# IAMP.net
KiCad netlist of a schematic drawn in Altium Designer
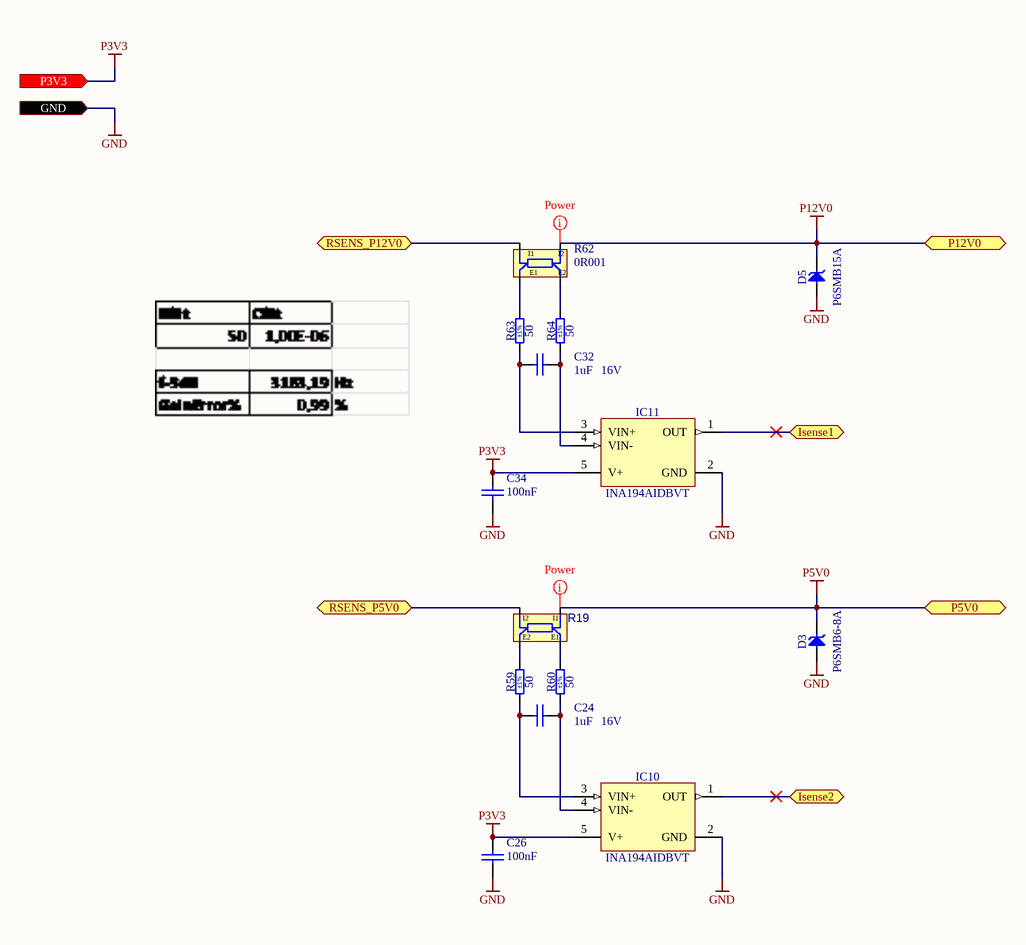
[diagram p0: IAMP.SchDoc]

(export (version "E")
  (design (tool "Eeschema 10.0.6"))
  (components
    (comp (ref "C24")
      (value "1uF")
      (footprint "CAPC1608X87N")
      (description "Non-polarised capacitor")
      (fields
        (field (name "PART NUMBER") "CC0603_1UF_16V_10%_X7R")
        (field (name "VOLTAGE") "16V")
        (field (name "TOLERANCE") "±10%")
        (field (name "AUTHOR") "CERN DEM JLC")
      )
      (libsource (lib "Capacitors") (part "Capacitor - non polarized"))
    )
    (comp (ref "C26")
      (value "100nF")
      (footprint "CAPC1608X87N")
      (description "Non-polarised capacitor")
      (fields
        (field (name "PART NUMBER") "CC0603_100NF_50V_10%_X5R")
        (field (name "VOLTAGE") "50V")
        (field (name "AUTHOR") "CERN DEM MR")
      )
      (libsource (lib "Capacitors") (part "Capacitor - non polarized"))
    )
    (comp (ref "C32")
      (value "1uF")
      (footprint "CAPC1608X87N")
      (description "Non-polarised capacitor")
      (fields
        (field (name "PART NUMBER") "CC0603_1UF_16V_10%_X7R")
        (field (name "VOLTAGE") "16V")
        (field (name "TOLERANCE") "±10%")
        (field (name "AUTHOR") "CERN DEM JLC")
      )
      (libsource (lib "Capacitors") (part "Capacitor - non polarized"))
    )
    (comp (ref "C34")
      (value "100nF")
      (footprint "CAPC1608X87N")
      (description "Non-polarised capacitor")
      (fields
        (field (name "PART NUMBER") "CC0603_100NF_50V_10%_X5R")
        (field (name "VOLTAGE") "50V")
        (field (name "AUTHOR") "CERN DEM MR")
      )
      (libsource (lib "Capacitors") (part "Capacitor - non polarized"))
    )
    (comp (ref "D3")
      (value "P6SMB6-8A")
      (footprint "DIOM5436X261N")
      (description "10.5V Clamp 58.1A Ipp Tvs Diode Surface Mount SMB")
      (fields (field (name "VOLTAGE") "15V") (field (name "POWER") "600W") (field (name "AUTHOR") "LPA"))
      (libsource (lib "DIOT_PSU") (part "P6SMB6-8A"))
    )
    (comp (ref "D5")
      (value "P6SMB15A")
      (footprint "DIOM5436X261N")
      (description "Transient Voltage Suppressor Diode (Uni-Directional)")
      (fields
        (field (name "VOLTAGE") "15V")
        (field (name "POWER") "600W")
        (field (name "AUTHOR") "CERN DEM JLC")
      )
      (libsource (lib "ICs And Semiconductors") (part "Diode TVS Uni-Directional"))
    )
    (comp (ref "IC10")
      (value "INA194AIDBVT")
      (footprint "SOT95P280X145-5N")
      (description "Current Shunt Monitor -16V to +80V Common-Mode Range")
      (fields
        (field (name "MANUFACTURER") "TEXAS INSTRUMENTS")
        (field (name "MANUFACTURER PART NUMBER") "INA194AIDBV")
        (field (name "AUTHOR") "CERN DEM JLC")
      )
      (libsource (lib "ICs And Semiconductors") (part "INA194"))
    )
    (comp (ref "IC11")
      (value "INA194AIDBVT")
      (footprint "SOT95P280X145-5N")
      (description "Current Shunt Monitor -16V to +80V Common-Mode Range")
      (fields
        (field (name "MANUFACTURER") "TEXAS INSTRUMENTS")
        (field (name "MANUFACTURER PART NUMBER") "INA194AIDBV")
        (field (name "AUTHOR") "CERN DEM JLC")
      )
      (libsource (lib "ICs And Semiconductors") (part "INA194"))
    )
    (comp (ref "R19")
      (value "FC4TR100DER")
      (footprint "FC4TR100DER")
      (description "Fixed Resistor, Metal Foil, 0.5W, 0.1ohm, 0.5% +/-Tol, 50ppm/Cel, Surface Mount, 1206")
      (libsource (lib "TechnoSystem Workspace") (part "FC4TR100DER"))
    )
    (comp (ref "R59")
      (value "50")
      (footprint "RESC1608X55N")
      (description "Resistor - 1%")
      (fields
        (field (name "TOLERANCE") "±1%")
        (field (name "PART NUMBER") "R0603_50R_1%_0.1W_100PPM")
        (field (name "POWER") "0.1W")
        (field (name "AUTHOR") "CERN DEM MR")
      )
      (libsource (lib "Resistors") (part "Resistor - 1%"))
    )
    (comp (ref "R60")
      (value "50")
      (footprint "RESC1608X55N")
      (description "Resistor - 1%")
      (fields
        (field (name "TOLERANCE") "±1%")
        (field (name "PART NUMBER") "R0603_50R_1%_0.1W_100PPM")
        (field (name "POWER") "0.1W")
        (field (name "AUTHOR") "CERN DEM MR")
      )
      (libsource (lib "Resistors") (part "Resistor - 1%"))
    )
    (comp (ref "R62")
      (value "0R001")
      (footprint "RES_VISHAY_WSL3637_0R001-0R0019")
      (description "Power and Current Sensing Resistor")
      (fields
        (field (name "PART NUMBER") "R3637_0R001_1%_3W_50PPM_VISHAY_WSL3637")
        (field (name "POWER") "3W")
        (field (name "AUTHOR") "CERN DEM MR")
      )
      (libsource (lib "Resistors") (part "Current Sense Resistor"))
    )
    (comp (ref "R63")
      (value "50")
      (footprint "RESC1608X55N")
      (description "Resistor - 1%")
      (fields
        (field (name "TOLERANCE") "±1%")
        (field (name "PART NUMBER") "R0603_50R_1%_0.1W_100PPM")
        (field (name "POWER") "0.1W")
        (field (name "AUTHOR") "CERN DEM MR")
      )
      (libsource (lib "Resistors") (part "Resistor - 1%"))
    )
    (comp (ref "R64")
      (value "50")
      (footprint "RESC1608X55N")
      (description "Resistor - 1%")
      (fields
        (field (name "TOLERANCE") "±1%")
        (field (name "PART NUMBER") "R0603_50R_1%_0.1W_100PPM")
        (field (name "POWER") "0.1W")
        (field (name "AUTHOR") "CERN DEM MR")
      )
      (libsource (lib "Resistors") (part "Resistor - 1%"))
    )
  )
  (nets
    (net (code "1") (name "/Isense1") (class "Default")
      (node (ref "IC11") (pin "1") (pinfunction "OUT_1") (pintype "output"))
    )
    (net (code "2") (name "/Isense2") (class "Default")
      (node (ref "IC10") (pin "1") (pinfunction "OUT_1") (pintype "output"))
    )
    (net (code "3") (name "/RSENS_P5V0") (class "Default")
      (node (ref "R19") (pin "I2") (pinfunction "I2_I2") (pintype "passive"))
    )
    (net (code "4") (name "/RSENS_P12V0") (class "Default")
      (node (ref "R62") (pin "I1") (pinfunction "I1_I1") (pintype "passive"))
    )
    (net (code "5") (name "GND") (class "Default")
      (node (ref "C26") (pin "2") (pinfunction "2_2") (pintype "passive"))
      (node (ref "C34") (pin "2") (pinfunction "2_2") (pintype "passive"))
      (node (ref "D3") (pin "2") (pinfunction "A_2") (pintype "passive"))
      (node (ref "D5") (pin "2") (pinfunction "A_2") (pintype "passive"))
      (node (ref "IC10") (pin "2") (pinfunction "GND_2") (pintype "power_in"))
      (node (ref "IC11") (pin "2") (pinfunction "GND_2") (pintype "power_in"))
    )
    (net (code "6") (name "Net-(IC10-VIN+)") (class "Default")
      (node (ref "C24") (pin "1") (pinfunction "1_1") (pintype "passive"))
      (node (ref "IC10") (pin "3") (pinfunction "VIN+_3") (pintype "input"))
      (node (ref "R59") (pin "1") (pinfunction "1_1") (pintype "passive"))
    )
    (net (code "7") (name "Net-(IC10-VIN-)") (class "Default")
      (node (ref "C24") (pin "2") (pinfunction "2_2") (pintype "passive"))
      (node (ref "IC10") (pin "4") (pinfunction "VIN-_4") (pintype "input"))
      (node (ref "R60") (pin "1") (pinfunction "1_1") (pintype "passive"))
    )
    (net (code "8") (name "Net-(IC11-VIN+)") (class "Default")
      (node (ref "C32") (pin "1") (pinfunction "1_1") (pintype "passive"))
      (node (ref "IC11") (pin "3") (pinfunction "VIN+_3") (pintype "input"))
      (node (ref "R63") (pin "1") (pinfunction "1_1") (pintype "passive"))
    )
    (net (code "9") (name "Net-(IC11-VIN-)") (class "Default")
      (node (ref "C32") (pin "2") (pinfunction "2_2") (pintype "passive"))
      (node (ref "IC11") (pin "4") (pinfunction "VIN-_4") (pintype "input"))
      (node (ref "R64") (pin "1") (pinfunction "1_1") (pintype "passive"))
    )
    (net (code "10") (name "Net-(R19-PadE1)") (class "Default")
      (node (ref "R19") (pin "E1") (pinfunction "E1_E1") (pintype "passive"))
      (node (ref "R60") (pin "2") (pinfunction "2_2") (pintype "passive"))
    )
    (net (code "11") (name "Net-(R19-PadE2)") (class "Default")
      (node (ref "R19") (pin "E2") (pinfunction "E2_E2") (pintype "passive"))
      (node (ref "R59") (pin "2") (pinfunction "2_2") (pintype "passive"))
    )
    (net (code "12") (name "Net-(R62-PadE1)") (class "Default")
      (node (ref "R62") (pin "E1") (pinfunction "E1_E1") (pintype "passive"))
      (node (ref "R63") (pin "2") (pinfunction "2_2") (pintype "passive"))
    )
    (net (code "13") (name "Net-(R62-PadE2)") (class "Default")
      (node (ref "R62") (pin "E2") (pinfunction "E2_E2") (pintype "passive"))
      (node (ref "R64") (pin "2") (pinfunction "2_2") (pintype "passive"))
    )
    (net (code "14") (name "P3V3") (class "Default")
      (node (ref "C26") (pin "1") (pinfunction "1_1") (pintype "passive"))
      (node (ref "C34") (pin "1") (pinfunction "1_1") (pintype "passive"))
      (node (ref "IC10") (pin "5") (pinfunction "V+_5") (pintype "power_in"))
      (node (ref "IC11") (pin "5") (pinfunction "V+_5") (pintype "power_in"))
    )
    (net (code "15") (name "P5V0") (class "Default")
      (node (ref "D3") (pin "1") (pinfunction "C_1") (pintype "passive"))
      (node (ref "R19") (pin "I1") (pinfunction "I1_I1") (pintype "passive"))
    )
    (net (code "16") (name "P12V0") (class "Default")
      (node (ref "D5") (pin "1") (pinfunction "C_1") (pintype "passive"))
      (node (ref "R62") (pin "I2") (pinfunction "I2_I2") (pintype "passive"))
    )
  )
)
